# Thruster_V1_0.net
KiCad netlist of a schematic drawn in Altium Designer
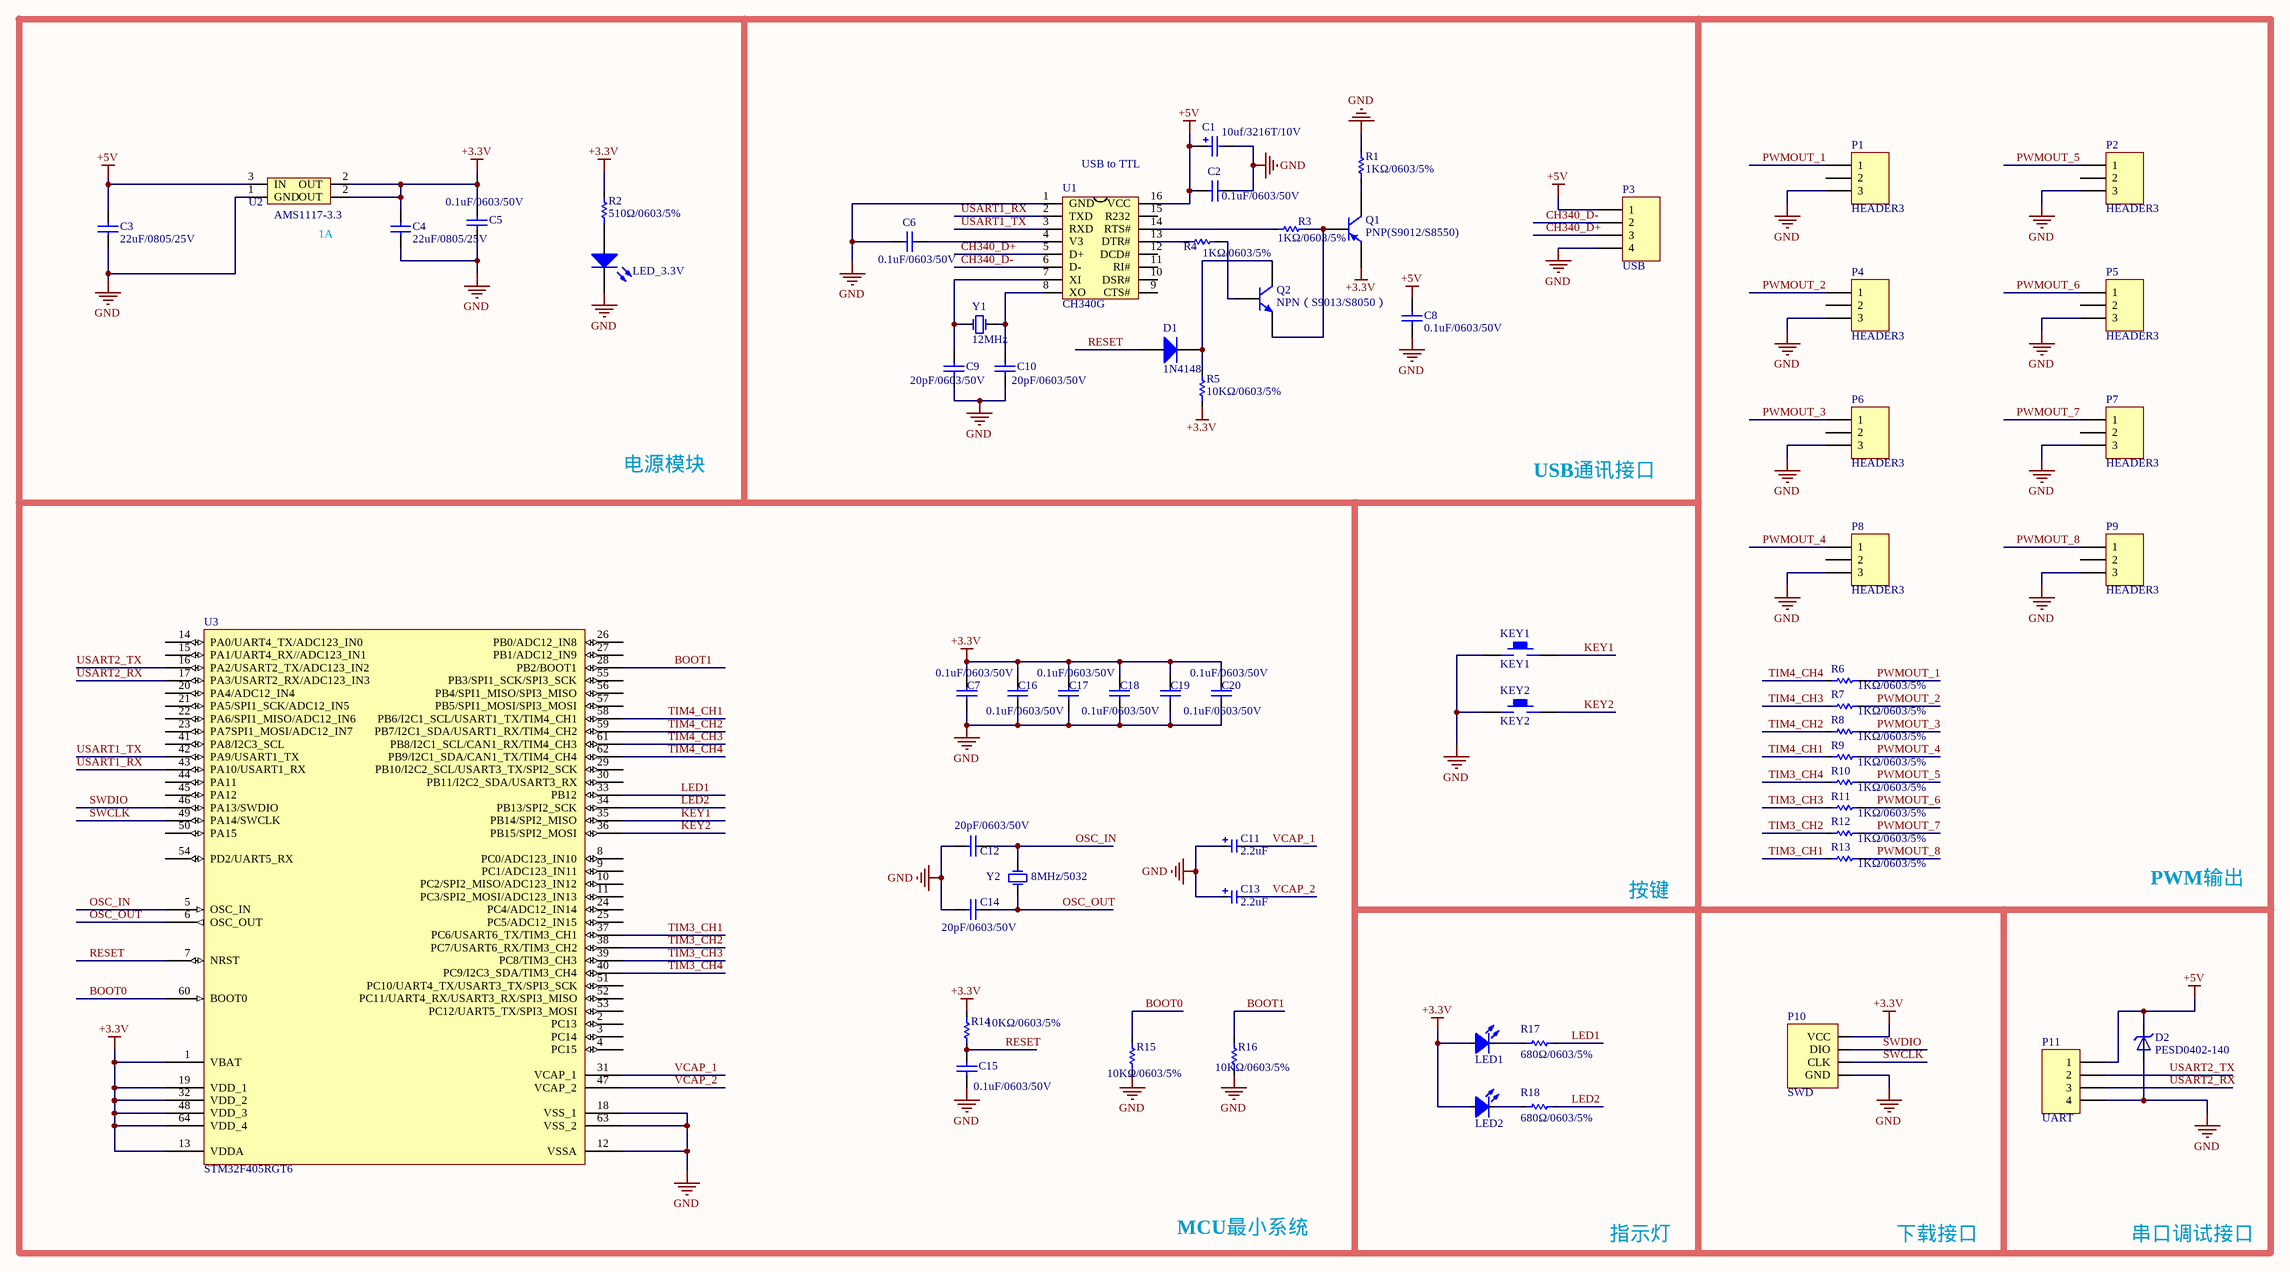
[diagram p0: Thruster_V1.0.SchDoc]

(export (version "E")
  (design (tool "Eeschema 10.0.6"))
  (components
    (comp (ref "C1")
      (value "10uf/3216T/10V")
      (footprint "Cap Poll 1(3216T)")
      (description "Polarized Capacitor (Surface Mount)(钽电容)")
      (libsource (lib "wgcoSchlib") (part "Cap Poll"))
    )
    (comp (ref "C2")
      (value "0.1uF/0603/50V")
      (footprint "0603C")
      (description "CAP 0805 0603 0402")
      (libsource (lib "wgcoSchlib") (part "CAP_0805/0603/0402"))
    )
    (comp (ref "C3")
      (value "22uF/0805/25V")
      (footprint "0805C")
      (description "CAP 0805 0603 0402")
      (fields (field (name "Comment") "CAP"))
      (libsource (lib "wgcoSchlib") (part "CAP_0805/0603/0402"))
    )
    (comp (ref "C4")
      (value "22uF/0805/25V")
      (footprint "0805C")
      (description "CAP 0805 0603 0402")
      (fields (field (name "Comment") "CAP"))
      (libsource (lib "wgcoSchlib") (part "CAP_0805/0603/0402"))
    )
    (comp (ref "C5")
      (value "0.1uF/0603/50V")
      (footprint "0603C")
      (description "CAP 0805 0603 0402")
      (libsource (lib "wgcoSchlib") (part "CAP_0805/0603/0402"))
    )
    (comp (ref "C6")
      (value "0.1uF/0603/50V")
      (footprint "0603C")
      (description "CAP 0805 0603 0402")
      (libsource (lib "wgcoSchlib") (part "CAP_0805/0603/0402"))
    )
    (comp (ref "C7")
      (value "0.1uF/0603/50V")
      (footprint "0603C")
      (description "CAP 0805 0603 0402")
      (libsource (lib "wgcoSchlib") (part "CAP_0805/0603/0402"))
    )
    (comp (ref "C8")
      (value "0.1uF/0603/50V")
      (footprint "0603C")
      (description "CAP 0805 0603 0402")
      (libsource (lib "wgcoSchlib") (part "CAP_0805/0603/0402"))
    )
    (comp (ref "C9")
      (value "20pF/0603/50V")
      (footprint "0603C")
      (description "CAP 0805 0603 0402")
      (libsource (lib "wgcoSchlib") (part "CAP_0805/0603/0402"))
    )
    (comp (ref "C10")
      (value "20pF/0603/50V")
      (footprint "0603C")
      (description "CAP 0805 0603 0402")
      (libsource (lib "wgcoSchlib") (part "CAP_0805/0603/0402"))
    )
    (comp (ref "C11")
      (value "2.2uF")
      (footprint "Cap_Tan_0805")
      (description "Polarized Capacitor (Surface Mount)(钽电容)")
      (fields (field (name "Comment") "Cap_Tan_0805"))
      (libsource (lib "wgcoSchlib") (part "Cap_Tan_0805"))
    )
    (comp (ref "C12")
      (value "20pF/0603/50V")
      (footprint "0603C")
      (description "CAP 0805 0603 0402")
      (libsource (lib "wgcoSchlib") (part "CAP_0805/0603/0402"))
    )
    (comp (ref "C13")
      (value "2.2uF")
      (footprint "Cap_Tan_0805")
      (description "Polarized Capacitor (Surface Mount)(钽电容)")
      (fields (field (name "Comment") "Cap_Tan_0805"))
      (libsource (lib "wgcoSchlib") (part "Cap_Tan_0805"))
    )
    (comp (ref "C14")
      (value "20pF/0603/50V")
      (footprint "0603C")
      (description "CAP 0805 0603 0402")
      (libsource (lib "wgcoSchlib") (part "CAP_0805/0603/0402"))
    )
    (comp (ref "C15")
      (value "0.1uF/0603/50V")
      (footprint "0603C")
      (description "CAP 0805 0603 0402")
      (libsource (lib "wgcoSchlib") (part "CAP_0805/0603/0402"))
    )
    (comp (ref "C16")
      (value "0.1uF/0603/50V")
      (footprint "0603C")
      (description "CAP 0805 0603 0402")
      (libsource (lib "wgcoSchlib") (part "CAP_0805/0603/0402"))
    )
    (comp (ref "C17")
      (value "0.1uF/0603/50V")
      (footprint "0603C")
      (description "CAP 0805 0603 0402")
      (libsource (lib "wgcoSchlib") (part "CAP_0805/0603/0402"))
    )
    (comp (ref "C18")
      (value "0.1uF/0603/50V")
      (footprint "0603C")
      (description "CAP 0805 0603 0402")
      (libsource (lib "wgcoSchlib") (part "CAP_0805/0603/0402"))
    )
    (comp (ref "C19")
      (value "0.1uF/0603/50V")
      (footprint "0603C")
      (description "CAP 0805 0603 0402")
      (libsource (lib "wgcoSchlib") (part "CAP_0805/0603/0402"))
    )
    (comp (ref "C20")
      (value "0.1uF/0603/50V")
      (footprint "0603C")
      (description "CAP 0805 0603 0402")
      (libsource (lib "wgcoSchlib") (part "CAP_0805/0603/0402"))
    )
    (comp (ref "D1") (value "1N4148") (footprint "1206D") (libsource (lib "wgcoSchlib") (part "D")))
    (comp (ref "D2")
      (value "PESD0402-140")
      (footprint "0402R")
      (description "TVS二极管")
      (libsource (lib "wgcoSchlib") (part "Diode-PESD0402-140"))
    )
    (comp (ref "KEY1")
      (value "KEY1")
      (footprint "button-3x4x2mm 2 Pad")
      (description "按键")
      (libsource (lib "wgcoSchlib") (part "KEY"))
    )
    (comp (ref "KEY2")
      (value "KEY2")
      (footprint "button-3x4x2mm 2 Pad")
      (description "按键")
      (libsource (lib "wgcoSchlib") (part "KEY"))
    )
    (comp (ref "LED1")
      (value "LED_0603")
      (footprint "LED_0603_BLUE")
      (description "LED")
      (libsource (lib "wgcoSchlib") (part "LED_0603"))
    )
    (comp (ref "LED2")
      (value "LED_0603")
      (footprint "LED_0603_RED")
      (description "LED")
      (libsource (lib "wgcoSchlib") (part "LED_0603"))
    )
    (comp (ref "LED_1")
      (value "LED_3.3V")
      (footprint "LED_0603_RED")
      (description "Typical RED, GREEN, YELLOW, AMBER GaAs LED")
      (libsource (lib "wgcoSchlib") (part "LED"))
    )
    (comp (ref "P1")
      (value "HEADER3")
      (footprint "HEADER3")
      (description "Header, 3-Pin")
      (libsource (lib "wgcoSchlib") (part "HEADER3"))
    )
    (comp (ref "P2")
      (value "HEADER3")
      (footprint "HEADER3")
      (description "Header, 3-Pin")
      (libsource (lib "wgcoSchlib") (part "HEADER3"))
    )
    (comp (ref "P3")
      (value "USB")
      (footprint "HEADER-GH1.25-4P")
      (description "Header, 4-Pin")
      (libsource (lib "wgcoSchlib") (part "HEADER4"))
    )
    (comp (ref "P4")
      (value "HEADER3")
      (footprint "HEADER3")
      (description "Header, 3-Pin")
      (libsource (lib "wgcoSchlib") (part "HEADER3"))
    )
    (comp (ref "P5")
      (value "HEADER3")
      (footprint "HEADER3")
      (description "Header, 3-Pin")
      (libsource (lib "wgcoSchlib") (part "HEADER3"))
    )
    (comp (ref "P6")
      (value "HEADER3")
      (footprint "HEADER3")
      (description "Header, 3-Pin")
      (libsource (lib "wgcoSchlib") (part "HEADER3"))
    )
    (comp (ref "P7")
      (value "HEADER3")
      (footprint "HEADER3")
      (description "Header, 3-Pin")
      (libsource (lib "wgcoSchlib") (part "HEADER3"))
    )
    (comp (ref "P8")
      (value "HEADER3")
      (footprint "HEADER3")
      (description "Header, 3-Pin")
      (libsource (lib "wgcoSchlib") (part "HEADER3"))
    )
    (comp (ref "P9")
      (value "HEADER3")
      (footprint "HEADER3")
      (description "Header, 3-Pin")
      (libsource (lib "wgcoSchlib") (part "HEADER3"))
    )
    (comp (ref "P10")
      (value "SWD")
      (footprint "HEADER-SH1.0-4P-A")
      (description "SWD调试下载接口")
      (libsource (lib "wgcoSchlib") (part "SWD-下载接口"))
    )
    (comp (ref "P11")
      (value "UART")
      (footprint "HEADER-GH1.25-4P")
      (description "Header, 4-Pin")
      (libsource (lib "") (part "HEADER4_1"))
    )
    (comp (ref "Q1")
      (value "PNP(S9012/S8550)")
      (footprint "NPN(S8050/S9103)贴片")
      (description "PNP Bipolar Transistor")
      (libsource (lib "wgcoSchlib") (part "PNP(S9012/S8550)"))
    )
    (comp (ref "Q2")
      (value "NPN（S9013/S8050）")
      (footprint "NPN(S8050/S9103)贴片")
      (description "NPN Bipolar Transistor")
      (libsource (lib "wgcoSchlib") (part "NPN(S9103/S8050)"))
    )
    (comp (ref "R1")
      (value "1KΩ/0603/5%")
      (footprint "0603R")
      (description "Resistor")
      (fields (field (name "POWER") "1/16W"))
      (libsource (lib "wgcoSchlib") (part "Res"))
    )
    (comp (ref "R2")
      (value "510Ω/0603/5%")
      (footprint "0603R")
      (description "Resistor")
      (fields (field (name "POWER") "1/16W"))
      (libsource (lib "wgcoSchlib") (part "Res"))
    )
    (comp (ref "R3")
      (value "1KΩ/0603/5%")
      (footprint "0603R")
      (description "Resistor")
      (fields (field (name "POWER") "1/16W"))
      (libsource (lib "wgcoSchlib") (part "Res"))
    )
    (comp (ref "R4")
      (value "1KΩ/0603/5%")
      (footprint "0603R")
      (description "Resistor")
      (fields (field (name "POWER") "1/16W"))
      (libsource (lib "wgcoSchlib") (part "Res"))
    )
    (comp (ref "R5")
      (value "10KΩ/0603/5%")
      (footprint "0603R")
      (description "Resistor")
      (fields (field (name "POWER") "1/16W"))
      (libsource (lib "wgcoSchlib") (part "Res"))
    )
    (comp (ref "R6")
      (value "1KΩ/0603/5%")
      (footprint "0603R")
      (description "Resistor")
      (fields (field (name "POWER") "1/16W"))
      (libsource (lib "wgcoSchlib") (part "Res"))
    )
    (comp (ref "R7")
      (value "1KΩ/0603/5%")
      (footprint "0603R")
      (description "Resistor")
      (fields (field (name "POWER") "1/16W"))
      (libsource (lib "wgcoSchlib") (part "Res"))
    )
    (comp (ref "R8")
      (value "1KΩ/0603/5%")
      (footprint "0603R")
      (description "Resistor")
      (fields (field (name "POWER") "1/16W"))
      (libsource (lib "wgcoSchlib") (part "Res"))
    )
    (comp (ref "R9")
      (value "1KΩ/0603/5%")
      (footprint "0603R")
      (description "Resistor")
      (fields (field (name "POWER") "1/16W"))
      (libsource (lib "wgcoSchlib") (part "Res"))
    )
    (comp (ref "R10")
      (value "1KΩ/0603/5%")
      (footprint "0603R")
      (description "Resistor")
      (fields (field (name "POWER") "1/16W"))
      (libsource (lib "wgcoSchlib") (part "Res"))
    )
    (comp (ref "R11")
      (value "1KΩ/0603/5%")
      (footprint "0603R")
      (description "Resistor")
      (fields (field (name "POWER") "1/16W"))
      (libsource (lib "wgcoSchlib") (part "Res"))
    )
    (comp (ref "R12")
      (value "1KΩ/0603/5%")
      (footprint "0603R")
      (description "Resistor")
      (fields (field (name "POWER") "1/16W"))
      (libsource (lib "wgcoSchlib") (part "Res"))
    )
    (comp (ref "R13")
      (value "1KΩ/0603/5%")
      (footprint "0603R")
      (description "Resistor")
      (fields (field (name "POWER") "1/16W"))
      (libsource (lib "wgcoSchlib") (part "Res"))
    )
    (comp (ref "R14")
      (value "10KΩ/0603/5%")
      (footprint "0603R")
      (description "Resistor")
      (fields (field (name "POWER") "1/16W"))
      (libsource (lib "wgcoSchlib") (part "Res"))
    )
    (comp (ref "R15")
      (value "10KΩ/0603/5%")
      (footprint "0603R")
      (description "Resistor")
      (fields (field (name "POWER") "1/16W"))
      (libsource (lib "wgcoSchlib") (part "Res"))
    )
    (comp (ref "R16")
      (value "10KΩ/0603/5%")
      (footprint "0603R")
      (description "Resistor")
      (fields (field (name "POWER") "1/16W"))
      (libsource (lib "wgcoSchlib") (part "Res"))
    )
    (comp (ref "R17")
      (value "680Ω/0603/5%")
      (footprint "0603R")
      (description "Resistor")
      (libsource (lib "wgcoSchlib") (part "Res"))
    )
    (comp (ref "R18")
      (value "680Ω/0603/5%")
      (footprint "0603R")
      (description "Resistor")
      (libsource (lib "wgcoSchlib") (part "Res"))
    )
    (comp (ref "U1")
      (value "CH340G")
      (footprint "SOP16M")
      (description "USB2UART")
      (libsource (lib "wgcoSchlib") (part "CH340G"))
    )
    (comp (ref "U2")
      (value "AMS1117-3.3")
      (footprint "AMS1117(SOT-223)")
      (libsource (lib "wgcoSchlib") (part "AMS1117"))
    )
    (comp (ref "U3")
      (value "STM32F405RGT6")
      (footprint "STM32_LQFP64")
      (description "STM32 ARM-based 32-bit MCU with 1024 Kbytes of Flash memory, 64-pin LQFP, Industrial Temperature")
      (libsource (lib "wgcoSchlib") (part "STM32F405RGT6"))
    )
    (comp (ref "Y1")
      (value "12MHz")
      (footprint "XT_5032_2P")
      (description "Crystal Oscillator")
      (fields (field (name "Comment") "12MHz/5032"))
      (libsource (lib "wgcoSchlib") (part "XTAL"))
    )
    (comp (ref "Y2")
      (value "8MHz/5032")
      (footprint "XT_5032_2P")
      (description "Crystal Oscillator")
      (libsource (lib "wgcoSchlib") (part "XTAL"))
    )
  )
  (nets
    (net (code "1") (name "+3.3V") (class "Default")
      (node (ref "C16") (pin "1") (pinfunction "1_1") (pintype "passive"))
      (node (ref "C17") (pin "1") (pinfunction "1_1") (pintype "passive"))
      (node (ref "C18") (pin "1") (pinfunction "1_1") (pintype "passive"))
      (node (ref "C19") (pin "1") (pinfunction "1_1") (pintype "passive"))
      (node (ref "C20") (pin "1") (pinfunction "1_1") (pintype "passive"))
      (node (ref "C4") (pin "2") (pinfunction "2_2") (pintype "passive"))
      (node (ref "C5") (pin "1") (pinfunction "1_1") (pintype "passive"))
      (node (ref "C7") (pin "1") (pinfunction "1_1") (pintype "passive"))
      (node (ref "LED1") (pin "1") (pinfunction "A_1") (pintype "passive"))
      (node (ref "LED2") (pin "1") (pinfunction "A_1") (pintype "passive"))
      (node (ref "P10") (pin "1") (pinfunction "VCC_1") (pintype "passive"))
      (node (ref "Q1") (pin "E") (pinfunction "E_E") (pintype "passive"))
      (node (ref "R14") (pin "2") (pinfunction "2_2") (pintype "passive"))
      (node (ref "R2") (pin "2") (pinfunction "2_2") (pintype "passive"))
      (node (ref "R5") (pin "2") (pinfunction "2_2") (pintype "passive"))
      (node (ref "U2") (pin "2") (pinfunction "OUT_2") (pintype "passive"))
      (node (ref "U3") (pin "1") (pinfunction "VBAT_1") (pintype "power_in"))
      (node (ref "U3") (pin "13") (pinfunction "VDDA_13") (pintype "power_in"))
      (node (ref "U3") (pin "19") (pinfunction "VDD_1_19") (pintype "power_in"))
      (node (ref "U3") (pin "32") (pinfunction "VDD_2_32") (pintype "power_in"))
      (node (ref "U3") (pin "48") (pinfunction "VDD_3_48") (pintype "power_in"))
      (node (ref "U3") (pin "64") (pinfunction "VDD_4_64") (pintype "power_in"))
    )
    (net (code "2") (name "+5V") (class "Default")
      (node (ref "C1") (pin "1") (pinfunction "1_1") (pintype "passive"))
      (node (ref "C2") (pin "1") (pinfunction "1_1") (pintype "passive"))
      (node (ref "C3") (pin "2") (pinfunction "2_2") (pintype "passive"))
      (node (ref "C8") (pin "2") (pinfunction "2_2") (pintype "passive"))
      (node (ref "D2") (pin "2") (pinfunction "K_2") (pintype "passive"))
      (node (ref "P11") (pin "1") (pinfunction "1_1") (pintype "passive"))
      (node (ref "P3") (pin "1") (pinfunction "1_1") (pintype "passive"))
      (node (ref "U1") (pin "16") (pinfunction "VCC_16") (pintype "passive"))
      (node (ref "U2") (pin "3") (pinfunction "IN_3") (pintype "passive"))
    )
    (net (code "3") (name "/BOOT0") (class "Default")
      (node (ref "R15") (pin "2") (pinfunction "2_2") (pintype "passive"))
      (node (ref "U3") (pin "60") (pinfunction "BOOT0_60") (pintype "input"))
    )
    (net (code "4") (name "/BOOT1") (class "Default")
      (node (ref "R16") (pin "2") (pinfunction "2_2") (pintype "passive"))
      (node (ref "U3") (pin "28") (pinfunction "PB2/BOOT1_28") (pintype "bidirectional"))
    )
    (net (code "5") (name "/CH340_D+") (class "Default")
      (node (ref "P3") (pin "3") (pinfunction "3_3") (pintype "passive"))
      (node (ref "U1") (pin "5") (pinfunction "D+_5") (pintype "passive"))
    )
    (net (code "6") (name "/CH340_D-") (class "Default")
      (node (ref "P3") (pin "2") (pinfunction "2_2") (pintype "passive"))
      (node (ref "U1") (pin "6") (pinfunction "D-_6") (pintype "passive"))
    )
    (net (code "7") (name "/KEY1") (class "Default")
      (node (ref "KEY1") (pin "2") (pinfunction "2_2") (pintype "passive"))
      (node (ref "U3") (pin "35") (pinfunction "PB14/SPI2_MISO_35") (pintype "bidirectional"))
    )
    (net (code "8") (name "/KEY2") (class "Default")
      (node (ref "KEY2") (pin "2") (pinfunction "2_2") (pintype "passive"))
      (node (ref "U3") (pin "36") (pinfunction "PB15/SPI2_MOSI_36") (pintype "bidirectional"))
    )
    (net (code "9") (name "/LED1") (class "Default")
      (node (ref "R17") (pin "1") (pinfunction "1_1") (pintype "passive"))
      (node (ref "U3") (pin "33") (pinfunction "PB12_33") (pintype "bidirectional"))
    )
    (net (code "10") (name "/LED2") (class "Default")
      (node (ref "R18") (pin "1") (pinfunction "1_1") (pintype "passive"))
      (node (ref "U3") (pin "34") (pinfunction "PB13/SPI2_SCK_34") (pintype "bidirectional"))
    )
    (net (code "11") (name "/OSC_IN") (class "Default")
      (node (ref "C12") (pin "2") (pinfunction "2_2") (pintype "passive"))
      (node (ref "U3") (pin "5") (pinfunction "OSC_IN_5") (pintype "input"))
      (node (ref "Y2") (pin "2") (pinfunction "OSC2_2") (pintype "passive"))
    )
    (net (code "12") (name "/OSC_OUT") (class "Default")
      (node (ref "C14") (pin "2") (pinfunction "2_2") (pintype "passive"))
      (node (ref "U3") (pin "6") (pinfunction "OSC_OUT_6") (pintype "output"))
      (node (ref "Y2") (pin "1") (pinfunction "OSC1_1") (pintype "passive"))
    )
    (net (code "13") (name "/PWMOUT_1") (class "Default")
      (node (ref "P1") (pin "1") (pinfunction "1_1") (pintype "passive"))
      (node (ref "R6") (pin "1") (pinfunction "1_1") (pintype "passive"))
    )
    (net (code "14") (name "/PWMOUT_2") (class "Default")
      (node (ref "P4") (pin "1") (pinfunction "1_1") (pintype "passive"))
      (node (ref "R7") (pin "1") (pinfunction "1_1") (pintype "passive"))
    )
    (net (code "15") (name "/PWMOUT_3") (class "Default")
      (node (ref "P6") (pin "1") (pinfunction "1_1") (pintype "passive"))
      (node (ref "R8") (pin "1") (pinfunction "1_1") (pintype "passive"))
    )
    (net (code "16") (name "/PWMOUT_4") (class "Default")
      (node (ref "P8") (pin "1") (pinfunction "1_1") (pintype "passive"))
      (node (ref "R9") (pin "1") (pinfunction "1_1") (pintype "passive"))
    )
    (net (code "17") (name "/PWMOUT_5") (class "Default")
      (node (ref "P2") (pin "1") (pinfunction "1_1") (pintype "passive"))
      (node (ref "R10") (pin "1") (pinfunction "1_1") (pintype "passive"))
    )
    (net (code "18") (name "/PWMOUT_6") (class "Default")
      (node (ref "P5") (pin "1") (pinfunction "1_1") (pintype "passive"))
      (node (ref "R11") (pin "1") (pinfunction "1_1") (pintype "passive"))
    )
    (net (code "19") (name "/PWMOUT_7") (class "Default")
      (node (ref "P7") (pin "1") (pinfunction "1_1") (pintype "passive"))
      (node (ref "R12") (pin "1") (pinfunction "1_1") (pintype "passive"))
    )
    (net (code "20") (name "/PWMOUT_8") (class "Default")
      (node (ref "P9") (pin "1") (pinfunction "1_1") (pintype "passive"))
      (node (ref "R13") (pin "1") (pinfunction "1_1") (pintype "passive"))
    )
    (net (code "21") (name "/RESET") (class "Default")
      (node (ref "C15") (pin "1") (pinfunction "1_1") (pintype "passive"))
      (node (ref "D1") (pin "1") (pinfunction "A_1") (pintype "passive"))
      (node (ref "R14") (pin "1") (pinfunction "1_1") (pintype "passive"))
      (node (ref "U3") (pin "7") (pinfunction "NRST_7") (pintype "bidirectional"))
    )
    (net (code "22") (name "/SWCLK") (class "Default")
      (node (ref "P10") (pin "2") (pinfunction "CLK_2") (pintype "passive"))
      (node (ref "U3") (pin "49") (pinfunction "PA14/SWCLK_49") (pintype "bidirectional"))
    )
    (net (code "23") (name "/SWDIO") (class "Default")
      (node (ref "P10") (pin "3") (pinfunction "DIO_3") (pintype "passive"))
      (node (ref "U3") (pin "46") (pinfunction "PA13/SWDIO_46") (pintype "bidirectional"))
    )
    (net (code "24") (name "/TIM3_CH1") (class "Default")
      (node (ref "R13") (pin "2") (pinfunction "2_2") (pintype "passive"))
      (node (ref "U3") (pin "37") (pinfunction "PC6/USART6_TX/TIM3_CH1_37") (pintype "bidirectional"))
    )
    (net (code "25") (name "/TIM3_CH2") (class "Default")
      (node (ref "R12") (pin "2") (pinfunction "2_2") (pintype "passive"))
      (node (ref "U3") (pin "38") (pinfunction "PC7/USART6_RX/TIM3_CH2_38") (pintype "bidirectional"))
    )
    (net (code "26") (name "/TIM3_CH3") (class "Default")
      (node (ref "R11") (pin "2") (pinfunction "2_2") (pintype "passive"))
      (node (ref "U3") (pin "39") (pinfunction "PC8/TIM3_CH3_39") (pintype "bidirectional"))
    )
    (net (code "27") (name "/TIM3_CH4") (class "Default")
      (node (ref "R10") (pin "2") (pinfunction "2_2") (pintype "passive"))
      (node (ref "U3") (pin "40") (pinfunction "PC9/I2C3_SDA/TIM3_CH4_40") (pintype "bidirectional"))
    )
    (net (code "28") (name "/TIM4_CH1") (class "Default")
      (node (ref "R9") (pin "2") (pinfunction "2_2") (pintype "passive"))
      (node (ref "U3") (pin "58") (pinfunction "PB6/I2C1_SCL/USART1_TX/TIM4_CH1_58") (pintype "bidirectional"))
    )
    (net (code "29") (name "/TIM4_CH2") (class "Default")
      (node (ref "R8") (pin "2") (pinfunction "2_2") (pintype "passive"))
      (node (ref "U3") (pin "59") (pinfunction "PB7/I2C1_SDA/USART1_RX/TIM4_CH2_59") (pintype "bidirectional"))
    )
    (net (code "30") (name "/TIM4_CH3") (class "Default")
      (node (ref "R7") (pin "2") (pinfunction "2_2") (pintype "passive"))
      (node (ref "U3") (pin "61") (pinfunction "PB8/I2C1_SCL/CAN1_RX/TIM4_CH3_61") (pintype "bidirectional"))
    )
    (net (code "31") (name "/TIM4_CH4") (class "Default")
      (node (ref "R6") (pin "2") (pinfunction "2_2") (pintype "passive"))
      (node (ref "U3") (pin "62") (pinfunction "PB9/I2C1_SDA/CAN1_TX/TIM4_CH4_62") (pintype "bidirectional"))
    )
    (net (code "32") (name "/USART1_RX") (class "Default")
      (node (ref "U1") (pin "2") (pinfunction "TXD_2") (pintype "passive"))
      (node (ref "U3") (pin "43") (pinfunction "PA10/USART1_RX_43") (pintype "bidirectional"))
    )
    (net (code "33") (name "/USART1_TX") (class "Default")
      (node (ref "U1") (pin "3") (pinfunction "RXD_3") (pintype "passive"))
      (node (ref "U3") (pin "42") (pinfunction "PA9/USART1_TX_42") (pintype "bidirectional"))
    )
    (net (code "34") (name "/USART2_RX") (class "Default")
      (node (ref "P11") (pin "3") (pinfunction "3_3") (pintype "passive"))
      (node (ref "U3") (pin "17") (pinfunction "PA3/USART2_RX/ADC123_IN3_17") (pintype "bidirectional"))
    )
    (net (code "35") (name "/USART2_TX") (class "Default")
      (node (ref "P11") (pin "2") (pinfunction "2_2") (pintype "passive"))
      (node (ref "U3") (pin "16") (pinfunction "PA2/USART2_TX/ADC123_IN2_16") (pintype "bidirectional"))
    )
    (net (code "36") (name "/VCAP_1") (class "Default")
      (node (ref "C11") (pin "2") (pinfunction "2_2") (pintype "passive"))
      (node (ref "U3") (pin "31") (pinfunction "VCAP_1_31") (pintype "power_in"))
    )
    (net (code "37") (name "/VCAP_2") (class "Default")
      (node (ref "C13") (pin "2") (pinfunction "2_2") (pintype "passive"))
      (node (ref "U3") (pin "47") (pinfunction "VCAP_2_47") (pintype "power_in"))
    )
    (net (code "38") (name "GND") (class "Default")
      (node (ref "C1") (pin "2") (pinfunction "2_2") (pintype "passive"))
      (node (ref "C10") (pin "1") (pinfunction "1_1") (pintype "passive"))
      (node (ref "C11") (pin "1") (pinfunction "1_1") (pintype "passive"))
      (node (ref "C12") (pin "1") (pinfunction "1_1") (pintype "passive"))
      (node (ref "C13") (pin "1") (pinfunction "1_1") (pintype "passive"))
      (node (ref "C14") (pin "1") (pinfunction "1_1") (pintype "passive"))
      (node (ref "C15") (pin "2") (pinfunction "2_2") (pintype "passive"))
      (node (ref "C16") (pin "2") (pinfunction "2_2") (pintype "passive"))
      (node (ref "C17") (pin "2") (pinfunction "2_2") (pintype "passive"))
      (node (ref "C18") (pin "2") (pinfunction "2_2") (pintype "passive"))
      (node (ref "C19") (pin "2") (pinfunction "2_2") (pintype "passive"))
      (node (ref "C2") (pin "2") (pinfunction "2_2") (pintype "passive"))
      (node (ref "C20") (pin "2") (pinfunction "2_2") (pintype "passive"))
      (node (ref "C3") (pin "1") (pinfunction "1_1") (pintype "passive"))
      (node (ref "C4") (pin "1") (pinfunction "1_1") (pintype "passive"))
      (node (ref "C5") (pin "2") (pinfunction "2_2") (pintype "passive"))
      (node (ref "C6") (pin "2") (pinfunction "2_2") (pintype "passive"))
      (node (ref "C7") (pin "2") (pinfunction "2_2") (pintype "passive"))
      (node (ref "C8") (pin "1") (pinfunction "1_1") (pintype "passive"))
      (node (ref "C9") (pin "1") (pinfunction "1_1") (pintype "passive"))
      (node (ref "D2") (pin "1") (pinfunction "A_1") (pintype "passive"))
      (node (ref "KEY1") (pin "1") (pinfunction "1_1") (pintype "passive"))
      (node (ref "KEY2") (pin "1") (pinfunction "1_1") (pintype "passive"))
      (node (ref "LED_1") (pin "2") (pinfunction "K_2") (pintype "passive"))
      (node (ref "P1") (pin "3") (pinfunction "3_3") (pintype "passive"))
      (node (ref "P10") (pin "4") (pinfunction "GND_4") (pintype "passive"))
      (node (ref "P11") (pin "4") (pinfunction "4_4") (pintype "passive"))
      (node (ref "P2") (pin "3") (pinfunction "3_3") (pintype "passive"))
      (node (ref "P3") (pin "4") (pinfunction "4_4") (pintype "passive"))
      (node (ref "P4") (pin "3") (pinfunction "3_3") (pintype "passive"))
      (node (ref "P5") (pin "3") (pinfunction "3_3") (pintype "passive"))
      (node (ref "P6") (pin "3") (pinfunction "3_3") (pintype "passive"))
      (node (ref "P7") (pin "3") (pinfunction "3_3") (pintype "passive"))
      (node (ref "P8") (pin "3") (pinfunction "3_3") (pintype "passive"))
      (node (ref "P9") (pin "3") (pinfunction "3_3") (pintype "passive"))
      (node (ref "R1") (pin "1") (pinfunction "1_1") (pintype "passive"))
      (node (ref "R15") (pin "1") (pinfunction "1_1") (pintype "passive"))
      (node (ref "R16") (pin "1") (pinfunction "1_1") (pintype "passive"))
      (node (ref "U1") (pin "1") (pinfunction "GND_1") (pintype "passive"))
      (node (ref "U2") (pin "1") (pinfunction "GND_1") (pintype "passive"))
      (node (ref "U3") (pin "12") (pinfunction "VSSA_12") (pintype "power_in"))
      (node (ref "U3") (pin "18") (pinfunction "VSS_1_18") (pintype "power_in"))
      (node (ref "U3") (pin "63") (pinfunction "VSS_2_63") (pintype "power_in"))
    )
    (net (code "39") (name "Net-(D1-K)") (class "Default")
      (node (ref "D1") (pin "2") (pinfunction "K_2") (pintype "passive"))
      (node (ref "Q2") (pin "C") (pinfunction "C_C") (pintype "passive"))
      (node (ref "R5") (pin "1") (pinfunction "1_1") (pintype "passive"))
    )
    (net (code "40") (name "Net-(LED1-K)") (class "Default")
      (node (ref "LED1") (pin "2") (pinfunction "K_2") (pintype "passive"))
      (node (ref "R17") (pin "2") (pinfunction "2_2") (pintype "passive"))
    )
    (net (code "41") (name "Net-(LED2-K)") (class "Default")
      (node (ref "LED2") (pin "2") (pinfunction "K_2") (pintype "passive"))
      (node (ref "R18") (pin "2") (pinfunction "2_2") (pintype "passive"))
    )
    (net (code "42") (name "Net-(LED_1-A)") (class "Default")
      (node (ref "LED_1") (pin "1") (pinfunction "A_1") (pintype "passive"))
      (node (ref "R2") (pin "1") (pinfunction "1_1") (pintype "passive"))
    )
    (net (code "43") (name "Net-(Q1-PadB)") (class "Default")
      (node (ref "Q1") (pin "B") (pinfunction "B_B") (pintype "passive"))
      (node (ref "Q2") (pin "E") (pinfunction "E_E") (pintype "passive"))
      (node (ref "R3") (pin "1") (pinfunction "1_1") (pintype "passive"))
    )
    (net (code "44") (name "Net-(Q1-PadC)") (class "Default")
      (node (ref "Q1") (pin "C") (pinfunction "C_C") (pintype "passive"))
      (node (ref "R1") (pin "2") (pinfunction "2_2") (pintype "passive"))
    )
    (net (code "45") (name "Net-(Q2-PadB)") (class "Default")
      (node (ref "Q2") (pin "B") (pinfunction "B_B") (pintype "passive"))
      (node (ref "R4") (pin "1") (pinfunction "1_1") (pintype "passive"))
    )
    (net (code "46") (name "Net-(U1-DTR#)") (class "Default")
      (node (ref "R4") (pin "2") (pinfunction "2_2") (pintype "passive"))
      (node (ref "U1") (pin "13") (pinfunction "DTR#_13") (pintype "passive"))
    )
    (net (code "47") (name "Net-(U1-RTS#)") (class "Default")
      (node (ref "R3") (pin "2") (pinfunction "2_2") (pintype "passive"))
      (node (ref "U1") (pin "14") (pinfunction "RTS#_14") (pintype "passive"))
    )
    (net (code "48") (name "Net-(U1-V3)") (class "Default")
      (node (ref "C6") (pin "1") (pinfunction "1_1") (pintype "passive"))
      (node (ref "U1") (pin "4") (pinfunction "V3_4") (pintype "passive"))
    )
    (net (code "49") (name "Net-(U1-XI)") (class "Default")
      (node (ref "C9") (pin "2") (pinfunction "2_2") (pintype "passive"))
      (node (ref "U1") (pin "7") (pinfunction "XI_7") (pintype "passive"))
      (node (ref "Y1") (pin "2") (pinfunction "OSC2_2") (pintype "passive"))
    )
    (net (code "50") (name "Net-(U1-XO)") (class "Default")
      (node (ref "C10") (pin "2") (pinfunction "2_2") (pintype "passive"))
      (node (ref "U1") (pin "8") (pinfunction "XO_8") (pintype "passive"))
      (node (ref "Y1") (pin "1") (pinfunction "OSC1_1") (pintype "passive"))
    )
    (net (code "51") (name "unconnected-(P1-Pad2)") (class "Default")
      (node (ref "P1") (pin "2") (pinfunction "2_2") (pintype "passive"))
    )
    (net (code "52") (name "unconnected-(P2-Pad2)") (class "Default")
      (node (ref "P2") (pin "2") (pinfunction "2_2") (pintype "passive"))
    )
    (net (code "53") (name "unconnected-(P4-Pad2)") (class "Default")
      (node (ref "P4") (pin "2") (pinfunction "2_2") (pintype "passive"))
    )
    (net (code "54") (name "unconnected-(P5-Pad2)") (class "Default")
      (node (ref "P5") (pin "2") (pinfunction "2_2") (pintype "passive"))
    )
    (net (code "55") (name "unconnected-(P6-Pad2)") (class "Default")
      (node (ref "P6") (pin "2") (pinfunction "2_2") (pintype "passive"))
    )
    (net (code "56") (name "unconnected-(P7-Pad2)") (class "Default")
      (node (ref "P7") (pin "2") (pinfunction "2_2") (pintype "passive"))
    )
    (net (code "57") (name "unconnected-(P8-Pad2)") (class "Default")
      (node (ref "P8") (pin "2") (pinfunction "2_2") (pintype "passive"))
    )
    (net (code "58") (name "unconnected-(P9-Pad2)") (class "Default")
      (node (ref "P9") (pin "2") (pinfunction "2_2") (pintype "passive"))
    )
    (net (code "59") (name "unconnected-(U1-CTS#-Pad9)") (class "Default")
      (node (ref "U1") (pin "9") (pinfunction "CTS#_9") (pintype "passive"))
    )
    (net (code "60") (name "unconnected-(U1-DCD#-Pad12)") (class "Default")
      (node (ref "U1") (pin "12") (pinfunction "DCD#_12") (pintype "passive"))
    )
    (net (code "61") (name "unconnected-(U1-DSR#-Pad10)") (class "Default")
      (node (ref "U1") (pin "10") (pinfunction "DSR#_10") (pintype "passive"))
    )
    (net (code "62") (name "unconnected-(U1-R232-Pad15)") (class "Default")
      (node (ref "U1") (pin "15") (pinfunction "R232_15") (pintype "passive"))
    )
    (net (code "63") (name "unconnected-(U1-RI#-Pad11)") (class "Default")
      (node (ref "U1") (pin "11") (pinfunction "RI#_11") (pintype "passive"))
    )
    (net (code "64") (name "unconnected-(U3-PA0{slash}UART4_TX{slash}ADC123_IN0-Pad14)") (class "Default")
      (node (ref "U3") (pin "14") (pinfunction "PA0/UART4_TX/ADC123_IN0_14") (pintype "bidirectional"))
    )
    (net (code "65") (name "unconnected-(U3-PA1{slash}UART4_RX{slash}{slash}ADC123_IN1-Pad15)") (class "Default")
      (node (ref "U3") (pin "15") (pinfunction "PA1/UART4_RX//ADC123_IN1_15") (pintype "bidirectional"))
    )
    (net (code "66") (name "unconnected-(U3-PA4{slash}ADC12_IN4-Pad20)") (class "Default")
      (node (ref "U3") (pin "20") (pinfunction "PA4/ADC12_IN4_20") (pintype "bidirectional"))
    )
    (net (code "67") (name "unconnected-(U3-PA5{slash}SPI1_SCK{slash}ADC12_IN5-Pad21)") (class "Default")
      (node (ref "U3") (pin "21") (pinfunction "PA5/SPI1_SCK/ADC12_IN5_21") (pintype "bidirectional"))
    )
    (net (code "68") (name "unconnected-(U3-PA6{slash}SPI1_MISO{slash}ADC12_IN6-Pad22)") (class "Default")
      (node (ref "U3") (pin "22") (pinfunction "PA6/SPI1_MISO/ADC12_IN6_22") (pintype "bidirectional"))
    )
    (net (code "69") (name "unconnected-(U3-PA7SPI1_MOSI{slash}ADC12_IN7-Pad23)") (class "Default")
      (node (ref "U3") (pin "23") (pinfunction "PA7SPI1_MOSI/ADC12_IN7_23") (pintype "bidirectional"))
    )
    (net (code "70") (name "unconnected-(U3-PA8{slash}I2C3_SCL-Pad41)") (class "Default")
      (node (ref "U3") (pin "41") (pinfunction "PA8/I2C3_SCL_41") (pintype "bidirectional"))
    )
    (net (code "71") (name "unconnected-(U3-PA11-Pad44)") (class "Default")
      (node (ref "U3") (pin "44") (pinfunction "PA11_44") (pintype "bidirectional"))
    )
    (net (code "72") (name "unconnected-(U3-PA12-Pad45)") (class "Default")
      (node (ref "U3") (pin "45") (pinfunction "PA12_45") (pintype "bidirectional"))
    )
    (net (code "73") (name "unconnected-(U3-PA15-Pad50)") (class "Default")
      (node (ref "U3") (pin "50") (pinfunction "PA15_50") (pintype "bidirectional"))
    )
    (net (code "74") (name "unconnected-(U3-PB0{slash}ADC12_IN8-Pad26)") (class "Default")
      (node (ref "U3") (pin "26") (pinfunction "PB0/ADC12_IN8_26") (pintype "bidirectional"))
    )
    (net (code "75") (name "unconnected-(U3-PB1{slash}ADC12_IN9-Pad27)") (class "Default")
      (node (ref "U3") (pin "27") (pinfunction "PB1/ADC12_IN9_27") (pintype "bidirectional"))
    )
    (net (code "76") (name "unconnected-(U3-PB3{slash}SPI1_SCK{slash}SPI3_SCK-Pad55)") (class "Default")
      (node (ref "U3") (pin "55") (pinfunction "PB3/SPI1_SCK/SPI3_SCK_55") (pintype "bidirectional"))
    )
    (net (code "77") (name "unconnected-(U3-PB4{slash}SPI1_MISO{slash}SPI3_MISO-Pad56)") (class "Default")
      (node (ref "U3") (pin "56") (pinfunction "PB4/SPI1_MISO/SPI3_MISO_56") (pintype "bidirectional"))
    )
    (net (code "78") (name "unconnected-(U3-PB5{slash}SPI1_MOSI{slash}SPI3_MOSI-Pad57)") (class "Default")
      (node (ref "U3") (pin "57") (pinfunction "PB5/SPI1_MOSI/SPI3_MOSI_57") (pintype "bidirectional"))
    )
    (net (code "79") (name "unconnected-(U3-PB10{slash}I2C2_SCL{slash}USART3_TX{slash}SPI2_SCK-Pad29)") (class "Default")
      (node (ref "U3") (pin "29") (pinfunction "PB10/I2C2_SCL/USART3_TX/SPI2_SCK_29") (pintype "bidirectional"))
    )
    (net (code "80") (name "unconnected-(U3-PB11{slash}I2C2_SDA{slash}USART3_RX-Pad30)") (class "Default")
      (node (ref "U3") (pin "30") (pinfunction "PB11/I2C2_SDA/USART3_RX_30") (pintype "bidirectional"))
    )
    (net (code "81") (name "unconnected-(U3-PC0{slash}ADC123_IN10-Pad8)") (class "Default")
      (node (ref "U3") (pin "8") (pinfunction "PC0/ADC123_IN10_8") (pintype "bidirectional"))
    )
    (net (code "82") (name "unconnected-(U3-PC1{slash}ADC123_IN11-Pad9)") (class "Default")
      (node (ref "U3") (pin "9") (pinfunction "PC1/ADC123_IN11_9") (pintype "bidirectional"))
    )
    (net (code "83") (name "unconnected-(U3-PC2{slash}SPI2_MISO{slash}ADC123_IN12-Pad10)") (class "Default")
      (node (ref "U3") (pin "10") (pinfunction "PC2/SPI2_MISO/ADC123_IN12_10") (pintype "bidirectional"))
    )
    (net (code "84") (name "unconnected-(U3-PC3{slash}SPI2_MOSI{slash}ADC123_IN13-Pad11)") (class "Default")
      (node (ref "U3") (pin "11") (pinfunction "PC3/SPI2_MOSI/ADC123_IN13_11") (pintype "bidirectional"))
    )
    (net (code "85") (name "unconnected-(U3-PC4{slash}ADC12_IN14-Pad24)") (class "Default")
      (node (ref "U3") (pin "24") (pinfunction "PC4/ADC12_IN14_24") (pintype "bidirectional"))
    )
    (net (code "86") (name "unconnected-(U3-PC5{slash}ADC12_IN15-Pad25)") (class "Default")
      (node (ref "U3") (pin "25") (pinfunction "PC5/ADC12_IN15_25") (pintype "bidirectional"))
    )
    (net (code "87") (name "unconnected-(U3-PC10{slash}UART4_TX{slash}USART3_TX{slash}SPI3_SCK-Pad51)") (class "Default")
      (node (ref "U3") (pin "51") (pinfunction "PC10/UART4_TX/USART3_TX/SPI3_SCK_51") (pintype "bidirectional"))
    )
    (net (code "88") (name "unconnected-(U3-PC11{slash}UART4_RX{slash}USART3_RX{slash}SPI3_MISO-Pad52)") (class "Default")
      (node (ref "U3") (pin "52") (pinfunction "PC11/UART4_RX/USART3_RX/SPI3_MISO_52") (pintype "bidirectional"))
    )
    (net (code "89") (name "unconnected-(U3-PC12{slash}UART5_TX{slash}SPI3_MOSI-Pad53)") (class "Default")
      (node (ref "U3") (pin "53") (pinfunction "PC12/UART5_TX/SPI3_MOSI_53") (pintype "bidirectional"))
    )
    (net (code "90") (name "unconnected-(U3-PC13-Pad2)") (class "Default")
      (node (ref "U3") (pin "2") (pinfunction "PC13_2") (pintype "bidirectional"))
    )
    (net (code "91") (name "unconnected-(U3-PC14-Pad3)") (class "Default")
      (node (ref "U3") (pin "3") (pinfunction "PC14_3") (pintype "bidirectional"))
    )
    (net (code "92") (name "unconnected-(U3-PC15-Pad4)") (class "Default")
      (node (ref "U3") (pin "4") (pinfunction "PC15_4") (pintype "bidirectional"))
    )
    (net (code "93") (name "unconnected-(U3-PD2{slash}UART5_RX-Pad54)") (class "Default")
      (node (ref "U3") (pin "54") (pinfunction "PD2/UART5_RX_54") (pintype "bidirectional"))
    )
  )
)
